# HGD_Update-20200515.net
KiCad netlist of a schematic drawn in Altium Designer
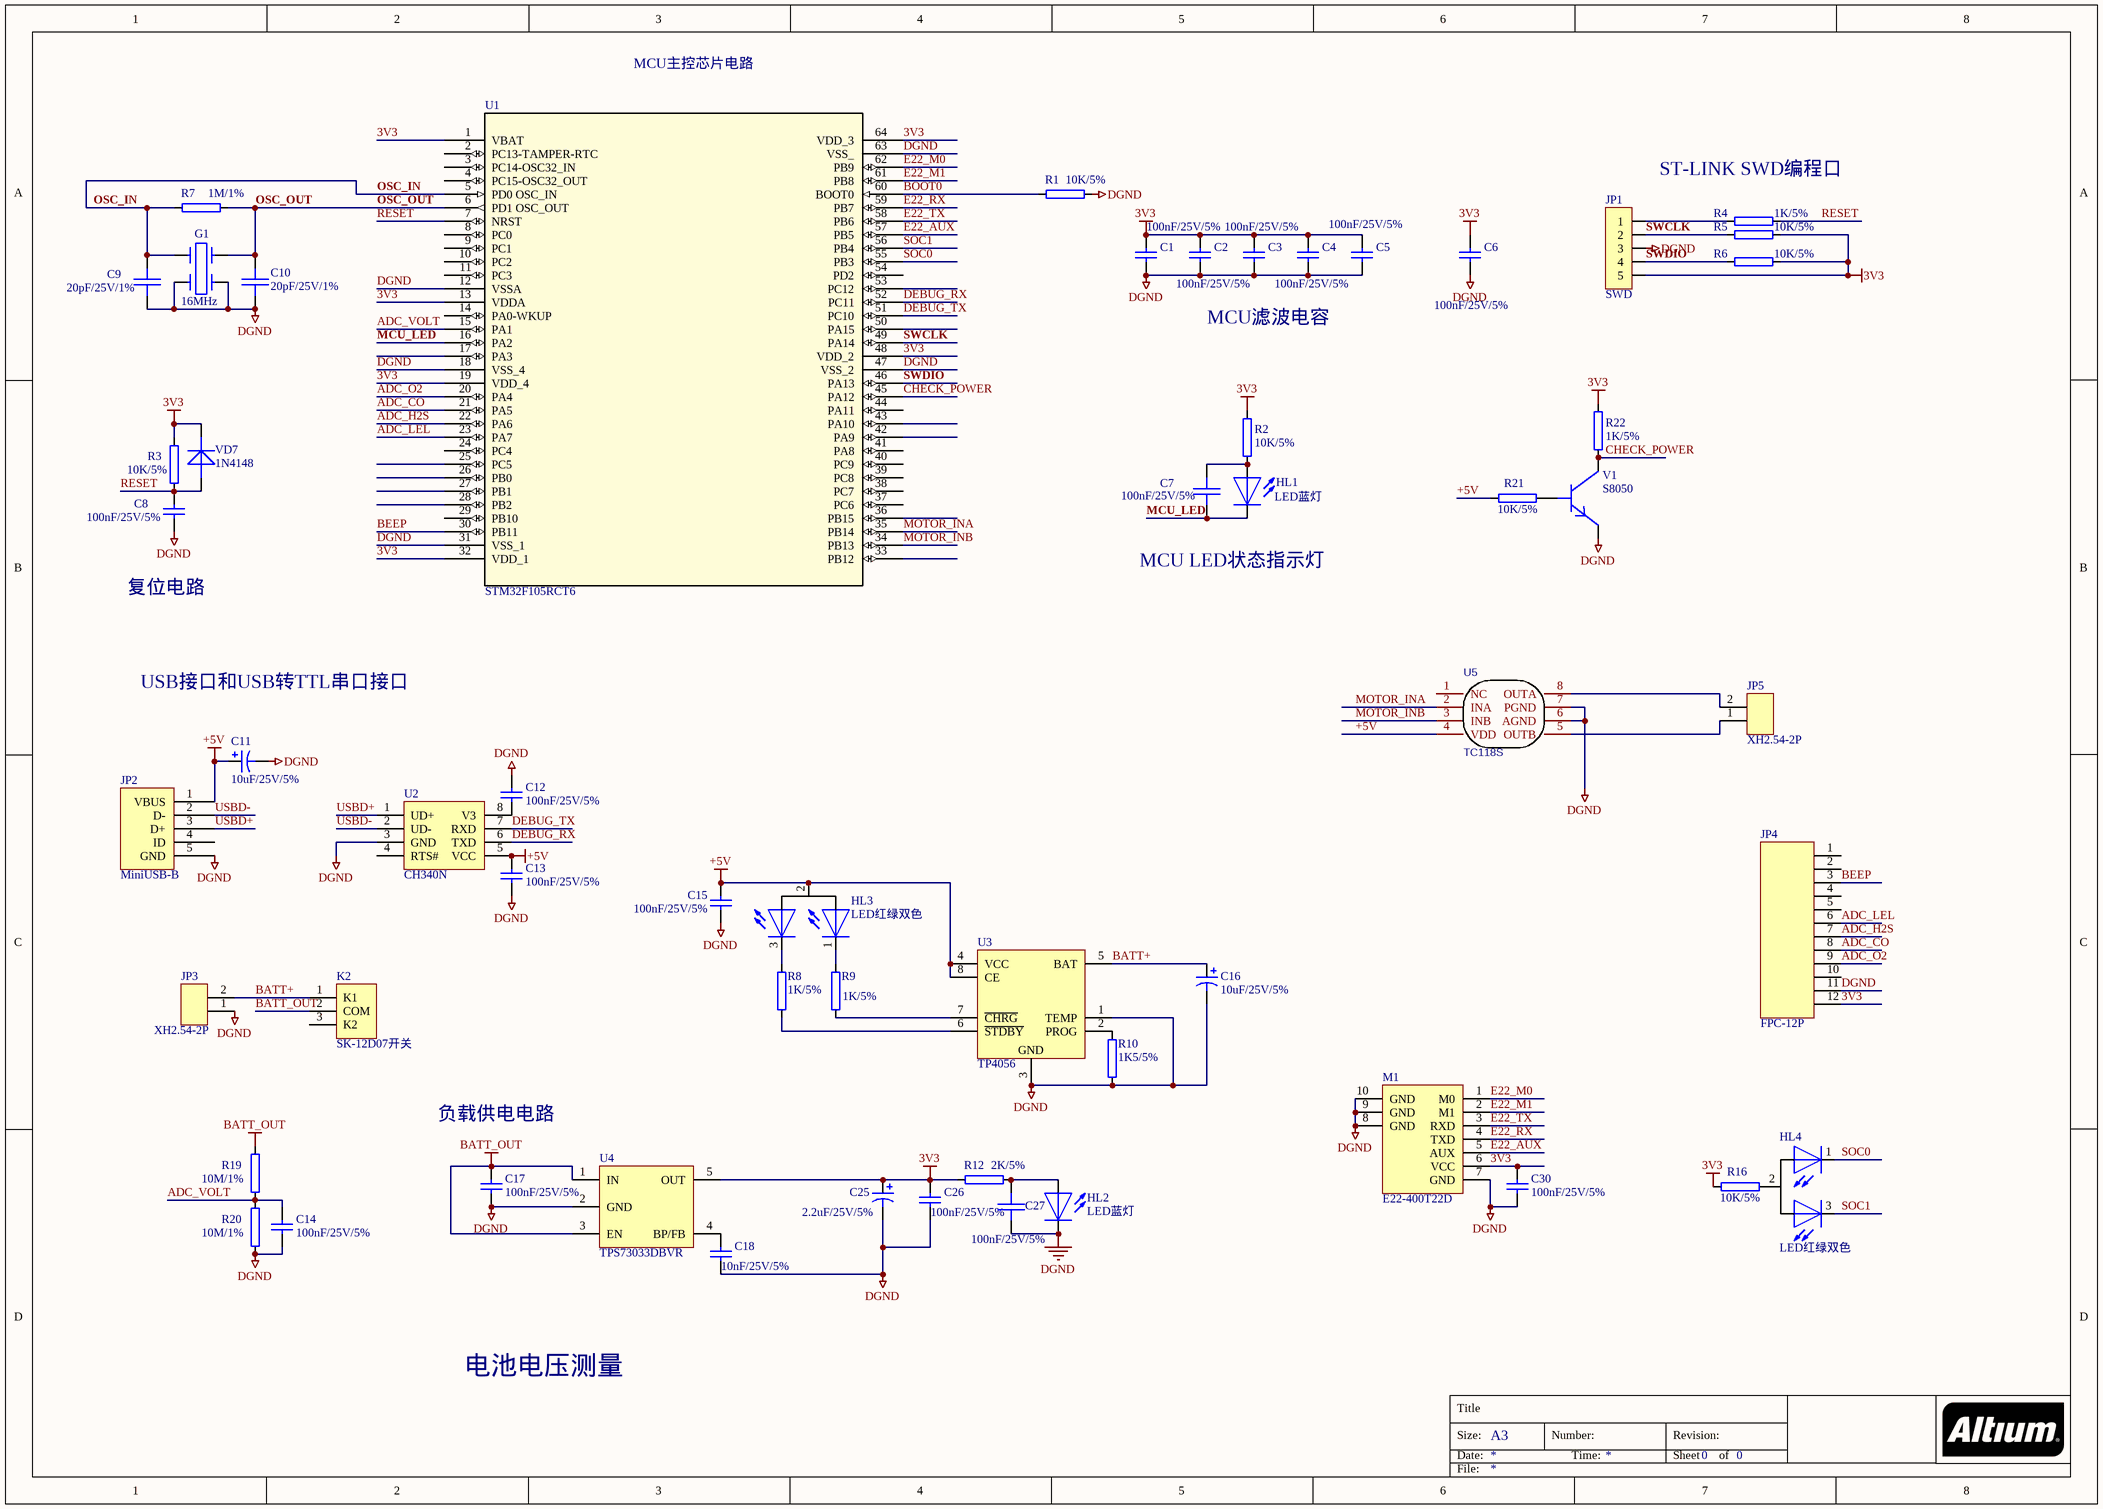
[diagram p0: HGD_Update-20200515.SchDoc]

(export (version "E")
  (design (tool "Eeschema 10.0.6"))
  (components
    (comp (ref "C1")
      (value "100nF/25V/5%")
      (footprint "C0603")
      (description "电容")
      (libsource (lib "*") (part "CAP-SMD"))
    )
    (comp (ref "C2")
      (value "100nF/25V/5%")
      (footprint "C0603")
      (description "电容")
      (libsource (lib "*") (part "CAP-SMD"))
    )
    (comp (ref "C3")
      (value "100nF/25V/5%")
      (footprint "C0603")
      (description "电容")
      (libsource (lib "*") (part "CAP-SMD"))
    )
    (comp (ref "C4")
      (value "100nF/25V/5%")
      (footprint "C0603")
      (description "电容")
      (libsource (lib "*") (part "CAP-SMD"))
    )
    (comp (ref "C5")
      (value "100nF/25V/5%")
      (footprint "C0603")
      (description "电容")
      (libsource (lib "*") (part "CAP-SMD"))
    )
    (comp (ref "C6")
      (value "100nF/25V/5%")
      (footprint "C0603")
      (description "电容")
      (libsource (lib "*") (part "CAP-SMD"))
    )
    (comp (ref "C7")
      (value "100nF/25V/5%")
      (footprint "C0603")
      (description "电容")
      (libsource (lib "*") (part "CAP"))
    )
    (comp (ref "C8")
      (value "100nF/25V/5%")
      (footprint "C0603")
      (description "电容")
      (libsource (lib "*") (part "CAP-SMD"))
    )
    (comp (ref "C9")
      (value "20pF/25V/1%")
      (footprint "C0603")
      (description "电容")
      (libsource (lib "ESSCH-Union") (part "CAP"))
    )
    (comp (ref "C10")
      (value "20pF/25V/1%")
      (footprint "C0603")
      (description "电容")
      (libsource (lib "ESSCH-Union") (part "CAP"))
    )
    (comp (ref "C11")
      (value "10uF/25V/5%")
      (footprint "C1206-1")
      (description "钽电容")
      (fields (field (name "PUBLISHER") "Altium Limited"))
      (libsource (lib "Miscellaneous Devices") (part "Cap Pol1"))
    )
    (comp (ref "C12")
      (value "100nF/25V/5%")
      (footprint "C0603")
      (description "电容")
      (fields (field (name "PUBLISHER") "Altium Limited"))
      (libsource (lib "Miscellaneous Devices") (part "Cap"))
    )
    (comp (ref "C13")
      (value "100nF/25V/5%")
      (footprint "C0603")
      (description "电容")
      (fields (field (name "PUBLISHER") "Altium Limited"))
      (libsource (lib "Miscellaneous Devices") (part "Cap"))
    )
    (comp (ref "C14") (value "100nF/25V/5%") (footprint "C0603") (libsource (lib "*") (part "CAP-SMD")))
    (comp (ref "C15")
      (value "100nF/25V/5%")
      (footprint "C0603")
      (description "电容")
      (fields (field (name "PUBLISHER") "Altium Limited"))
      (libsource (lib "Miscellaneous Devices") (part "Cap"))
    )
    (comp (ref "C16")
      (value "10uF/25V/5%")
      (footprint "C1206-1")
      (description "钽电容")
      (fields (field (name "PUBLISHER") "Altium Limited"))
      (libsource (lib "Miscellaneous Devices") (part "Cap Pol1"))
    )
    (comp (ref "C17") (value "100nF/25V/5%") (footprint "C0603") (libsource (lib "*") (part "CAP-SMD")))
    (comp (ref "C18")
      (value "10nF/25V/5%")
      (footprint "C0603")
      (description "电容")
      (fields (field (name "PUBLISHER") "Altium Limited"))
      (libsource (lib "Miscellaneous Devices") (part "Cap"))
    )
    (comp (ref "C25")
      (value "2.2uF/25V/5%")
      (footprint "C1206-1")
      (description "钽电容")
      (fields (field (name "PUBLISHER") "Altium Limited"))
      (libsource (lib "Miscellaneous Devices") (part "Cap Pol1"))
    )
    (comp (ref "C26")
      (value "100nF/25V/5%")
      (footprint "C0603")
      (description "电容")
      (fields (field (name "PUBLISHER") "Altium Limited"))
      (libsource (lib "Miscellaneous Devices") (part "Cap"))
    )
    (comp (ref "C27")
      (value "100nF/25V/5%")
      (footprint "C0603")
      (description "电容")
      (libsource (lib "*") (part "CAP"))
    )
    (comp (ref "C30")
      (value "100nF/25V/5%")
      (footprint "C0603")
      (description "电容")
      (fields (field (name "PUBLISHER") "Altium Limited"))
      (libsource (lib "Miscellaneous Devices") (part "Cap"))
    )
    (comp (ref "G1")
      (value "16MHz")
      (footprint "OSC5032")
      (description "两对电极压电晶体")
      (libsource (lib "ESSCH-Union") (part "CRYSTAL_4"))
    )
    (comp (ref "HL1")
      (value "LED蓝灯")
      (footprint "LED0603")
      (description "发光二极管")
      (libsource (lib "wypPCB_Lib") (part "发光二极管"))
    )
    (comp (ref "HL2")
      (value "LED蓝灯")
      (footprint "LED0603")
      (description "发光二极管")
      (libsource (lib "wypPCB_Lib") (part "发光二极管"))
    )
    (comp (ref "HL3")
      (value "LED红绿双色")
      (footprint "LED2_Common_Anode")
      (description "LED2_Common_Anode：双色LED，共阳极")
      (libsource (lib "") (part "LED2_Common_Anode_1"))
    )
    (comp (ref "HL4")
      (value "LED红绿双色")
      (footprint "LED2_Common_Anode")
      (description "LED2_Common_Anode：双色LED，共阳极")
      (libsource (lib "wypPCB_Lib") (part "LED2_Common_Anode"))
    )
    (comp (ref "JP1")
      (value "SWD")
      (footprint "XH2.54-5AW")
      (description "XH2.54-5P直插插针")
      (libsource (lib "wypPCB_Lib") (part "JP_XH2.54-5AW"))
    )
    (comp (ref "JP2")
      (value "MiniUSB-B")
      (footprint "MiniUSB-B")
      (description "MiniUSB-B母头插座")
      (libsource (lib "wypPCB_Lib") (part "MiniUSB-B"))
    )
    (comp (ref "JP3")
      (value "XH2.54-2P")
      (footprint "XH2.54-2AW")
      (description "XH2.54-2P弯针插座")
      (libsource (lib "") (part "XH2.54-2AW_1"))
    )
    (comp (ref "JP4")
      (value "FPC-12P")
      (footprint "FPC-1.0MM-12P-W")
      (libsource (lib "wypPCB_Lib") (part "FPC-12P"))
    )
    (comp (ref "JP5")
      (value "XH2.54-2P")
      (footprint "XH2.54-2AW")
      (description "XH2.54-2P弯针插座")
      (libsource (lib "wypPCB_Lib") (part "XH2.54-2AW"))
    )
    (comp (ref "K2")
      (value "SK-12D07开关")
      (footprint "SK-12D07")
      (description "SK-12D07：3脚2档小型拨动开关")
      (libsource (lib "WTME_PT100(v0.1)-20190512") (part "SK-12D07"))
    )
    (comp (ref "M1")
      (value "E22-400T22D")
      (footprint "E22-400T22D")
      (description "E22-400T22D LoRa模块")
      (libsource (lib "wypPCB_Lib") (part "E22-400T22D"))
    )
    (comp (ref "R1")
      (value "10K/5%")
      (footprint "R0603")
      (description "电阻")
      (libsource (lib "*") (part "RES2"))
    )
    (comp (ref "R2")
      (value "10K/5%")
      (footprint "R0603")
      (description "电阻")
      (libsource (lib "*") (part "RES2"))
    )
    (comp (ref "R3")
      (value "10K/5%")
      (footprint "R0603")
      (description "电阻")
      (libsource (lib "") (part "RES2_1"))
    )
    (comp (ref "R4")
      (value "1K/5%")
      (footprint "R0603")
      (description "电阻")
      (libsource (lib "") (part "RES2_1"))
    )
    (comp (ref "R5")
      (value "10K/5%")
      (footprint "R0603")
      (description "电阻")
      (libsource (lib "") (part "RES2_1"))
    )
    (comp (ref "R6")
      (value "10K/5%")
      (footprint "R0603")
      (description "电阻")
      (libsource (lib "") (part "RES2_1"))
    )
    (comp (ref "R7")
      (value "1M/1%")
      (footprint "R0603")
      (description "电阻")
      (libsource (lib "") (part "RES2_1"))
    )
    (comp (ref "R8")
      (value "1K/5%")
      (footprint "R0603")
      (description "电阻")
      (libsource (lib "") (part "RES2_2"))
    )
    (comp (ref "R9")
      (value "1K/5%")
      (footprint "R0603")
      (description "电阻")
      (libsource (lib "") (part "RES2_2"))
    )
    (comp (ref "R10")
      (value "1K5/5%")
      (footprint "R0603")
      (description "电阻")
      (libsource (lib "") (part "RES2_2"))
    )
    (comp (ref "R12")
      (value "2K/5%")
      (footprint "R0603")
      (description "电阻")
      (libsource (lib "*") (part "RES2"))
    )
    (comp (ref "R16")
      (value "10K/5%")
      (footprint "R0603")
      (description "电阻")
      (libsource (lib "*") (part "RES2"))
    )
    (comp (ref "R19")
      (value "10M/1%")
      (footprint "R0603")
      (description "电阻")
      (libsource (lib "*") (part "RES2"))
    )
    (comp (ref "R20")
      (value "10M/1%")
      (footprint "R0603")
      (description "电阻")
      (libsource (lib "*") (part "RES2"))
    )
    (comp (ref "R21")
      (value "10K/5%")
      (footprint "R0603")
      (description "电阻")
      (libsource (lib "") (part "RES2_1"))
    )
    (comp (ref "R22")
      (value "1K/5%")
      (footprint "R0603")
      (description "电阻")
      (libsource (lib "") (part "RES2_2"))
    )
    (comp (ref "U1")
      (value "STM32F105RCT6")
      (footprint "LQFP64_STM32F105R")
      (libsource (lib "wypPCB_Lib") (part "STM32F105RCT6"))
    )
    (comp (ref "U2")
      (value "CH340N")
      (footprint "CH340N_SOP8")
      (libsource (lib "wypPCB_Lib") (part "CH340N"))
    )
    (comp (ref "U3")
      (value "TP4056")
      (footprint "TP4056_SOP8_SOP127P600X175-8N")
      (libsource (lib "wypPCB_Lib") (part "TP4056"))
    )
    (comp (ref "U4")
      (value "TPS73033DBVR")
      (footprint "SGM2019_SOT23-5_95P280X125-5N")
      (description "SGM2019：Low Power, Low Dropout, RF Linear Regulators")
      (libsource (lib "wypPCB_Lib") (part "SGM2019"))
    )
    (comp (ref "U5")
      (value "TC118S")
      (footprint "SOP-8_L4.9-W3.9-P1.27-LS6.0-BL")
      (fields (field (name "BOM_SUPPLIER PART") "C88308"))
      (libsource (lib "HGD_Update_20200515") (part "TC118S"))
    )
    (comp (ref "V1")
      (value "S8050")
      (footprint "SOT-23")
      (description "NPN三极管")
      (libsource (lib "ESLIB(v1.1)-AD9-20150731") (part "NPN"))
    )
    (comp (ref "VD7")
      (value "1N4148")
      (footprint "LL-34")
      (description "开关二极管")
      (libsource (lib "wypPCB_Lib") (part "开关二极管"))
    )
  )
  (nets
    (net (code "1") (name "+5V") (class "Default")
      (node (ref "C11") (pin "1") (pinfunction "1_1") (pintype "passive"))
      (node (ref "C13") (pin "1") (pinfunction "1_1") (pintype "passive"))
      (node (ref "C15") (pin "1") (pinfunction "1_1") (pintype "passive"))
      (node (ref "HL3") (pin "2") (pinfunction "A_2") (pintype "passive"))
      (node (ref "JP2") (pin "1") (pinfunction "VBUS_1") (pintype "passive"))
      (node (ref "R21") (pin "2") (pintype "passive"))
      (node (ref "U2") (pin "5") (pinfunction "VCC_5") (pintype "passive"))
      (node (ref "U3") (pin "4") (pinfunction "VCC_4") (pintype "passive"))
      (node (ref "U3") (pin "8") (pinfunction "CE_8") (pintype "passive"))
      (node (ref "U5") (pin "4") (pinfunction "VDD_4") (pintype "passive"))
    )
    (net (code "2") (name "/ADC_CO") (class "Default")
      (node (ref "JP4") (pin "8") (pintype "passive"))
      (node (ref "U1") (pin "21") (pinfunction "PA5_21") (pintype "bidirectional"))
    )
    (net (code "3") (name "/ADC_H2S") (class "Default")
      (node (ref "JP4") (pin "7") (pintype "passive"))
      (node (ref "U1") (pin "22") (pinfunction "PA6_22") (pintype "bidirectional"))
    )
    (net (code "4") (name "/ADC_LEL") (class "Default")
      (node (ref "JP4") (pin "6") (pintype "passive"))
      (node (ref "U1") (pin "23") (pinfunction "PA7_23") (pintype "bidirectional"))
    )
    (net (code "5") (name "/ADC_O2") (class "Default")
      (node (ref "JP4") (pin "9") (pintype "passive"))
      (node (ref "U1") (pin "20") (pinfunction "PA4_20") (pintype "bidirectional"))
    )
    (net (code "6") (name "/ADC_VOLT") (class "Default")
      (node (ref "C14") (pin "1") (pintype "passive"))
      (node (ref "R19") (pin "2") (pintype "passive"))
      (node (ref "R20") (pin "1") (pintype "passive"))
      (node (ref "U1") (pin "15") (pinfunction "PA1_15") (pintype "bidirectional"))
    )
    (net (code "7") (name "/BATT+") (class "Default")
      (node (ref "C16") (pin "1") (pinfunction "1_1") (pintype "passive"))
      (node (ref "JP3") (pin "2") (pintype "passive"))
      (node (ref "K2") (pin "1") (pinfunction "K1_1") (pintype "passive"))
      (node (ref "U3") (pin "5") (pinfunction "BAT_5") (pintype "passive"))
    )
    (net (code "8") (name "/BEEP") (class "Default")
      (node (ref "JP4") (pin "3") (pintype "passive"))
      (node (ref "U1") (pin "30") (pinfunction "PB11_30") (pintype "bidirectional"))
    )
    (net (code "9") (name "/BOOT0") (class "Default")
      (node (ref "R1") (pin "2") (pintype "passive"))
      (node (ref "U1") (pin "60") (pinfunction "BOOT0_60") (pintype "input"))
    )
    (net (code "10") (name "/CHECK_POWER") (class "Default")
      (node (ref "R22") (pin "2") (pintype "passive"))
      (node (ref "U1") (pin "45") (pinfunction "PA12_45") (pintype "bidirectional"))
      (node (ref "V1") (pin "C") (pintype "passive"))
    )
    (net (code "11") (name "/DEBUG_RX") (class "Default")
      (node (ref "U1") (pin "52") (pinfunction "PC11_52") (pintype "bidirectional"))
      (node (ref "U2") (pin "6") (pinfunction "TXD_6") (pintype "passive"))
    )
    (net (code "12") (name "/DEBUG_TX") (class "Default")
      (node (ref "U1") (pin "51") (pinfunction "PC10_51") (pintype "bidirectional"))
      (node (ref "U2") (pin "7") (pinfunction "RXD_7") (pintype "passive"))
    )
    (net (code "13") (name "/E22_AUX") (class "Default")
      (node (ref "M1") (pin "5") (pinfunction "AUX_5") (pintype "passive"))
      (node (ref "U1") (pin "57") (pinfunction "PB5_57") (pintype "bidirectional"))
    )
    (net (code "14") (name "/E22_M0") (class "Default")
      (node (ref "M1") (pin "1") (pinfunction "M0_1") (pintype "passive"))
      (node (ref "U1") (pin "62") (pinfunction "PB9_62") (pintype "bidirectional"))
    )
    (net (code "15") (name "/E22_M1") (class "Default")
      (node (ref "M1") (pin "2") (pinfunction "M1_2") (pintype "passive"))
      (node (ref "U1") (pin "61") (pinfunction "PB8_61") (pintype "bidirectional"))
    )
    (net (code "16") (name "/E22_RX") (class "Default")
      (node (ref "M1") (pin "4") (pinfunction "TXD_4") (pintype "passive"))
      (node (ref "U1") (pin "59") (pinfunction "PB7_59") (pintype "bidirectional"))
    )
    (net (code "17") (name "/E22_TX") (class "Default")
      (node (ref "M1") (pin "3") (pinfunction "RXD_3") (pintype "passive"))
      (node (ref "U1") (pin "58") (pinfunction "PB6_58") (pintype "bidirectional"))
    )
    (net (code "18") (name "/MCU_LED") (class "Default")
      (node (ref "C7") (pin "2") (pintype "passive"))
      (node (ref "HL1") (pin "K") (pintype "passive"))
      (node (ref "U1") (pin "16") (pinfunction "PA2_16") (pintype "bidirectional"))
    )
    (net (code "19") (name "/MOTOR_INA") (class "Default")
      (node (ref "U1") (pin "35") (pinfunction "PB14_35") (pintype "bidirectional"))
      (node (ref "U5") (pin "2") (pinfunction "INA_2") (pintype "passive"))
    )
    (net (code "20") (name "/MOTOR_INB") (class "Default")
      (node (ref "U1") (pin "34") (pinfunction "PB13_34") (pintype "bidirectional"))
      (node (ref "U5") (pin "3") (pinfunction "INB_3") (pintype "passive"))
    )
    (net (code "21") (name "/OSC_IN") (class "Default")
      (node (ref "C9") (pin "2") (pintype "passive"))
      (node (ref "G1") (pin "1") (pintype "passive"))
      (node (ref "R7") (pin "1") (pintype "passive"))
      (node (ref "U1") (pin "5") (pinfunction "PD0_OSC_IN_5") (pintype "input"))
    )
    (net (code "22") (name "/OSC_OUT") (class "Default")
      (node (ref "C10") (pin "1") (pintype "passive"))
      (node (ref "G1") (pin "3") (pintype "passive"))
      (node (ref "R7") (pin "2") (pintype "passive"))
      (node (ref "U1") (pin "6") (pinfunction "PD1_OSC_OUT_6") (pintype "output"))
    )
    (net (code "23") (name "/RESET") (class "Default")
      (node (ref "C8") (pin "1") (pintype "passive"))
      (node (ref "R3") (pin "1") (pintype "passive"))
      (node (ref "R4") (pin "2") (pintype "passive"))
      (node (ref "U1") (pin "7") (pinfunction "NRST_7") (pintype "bidirectional"))
      (node (ref "VD7") (pin "A") (pintype "passive"))
    )
    (net (code "24") (name "/SOC0") (class "Default")
      (node (ref "HL4") (pin "1") (pinfunction "K1_1") (pintype "passive"))
      (node (ref "U1") (pin "55") (pinfunction "PB3_55") (pintype "bidirectional"))
    )
    (net (code "25") (name "/SOC1") (class "Default")
      (node (ref "HL4") (pin "3") (pinfunction "K2_3") (pintype "passive"))
      (node (ref "U1") (pin "56") (pinfunction "PB4_56") (pintype "bidirectional"))
    )
    (net (code "26") (name "/SWCLK") (class "Default")
      (node (ref "JP1") (pin "2") (pinfunction "2_2") (pintype "passive"))
      (node (ref "R5") (pin "1") (pintype "passive"))
      (node (ref "U1") (pin "49") (pinfunction "PA14_49") (pintype "bidirectional"))
    )
    (net (code "27") (name "/SWDIO") (class "Default")
      (node (ref "JP1") (pin "4") (pinfunction "4_4") (pintype "passive"))
      (node (ref "R6") (pin "1") (pintype "passive"))
      (node (ref "U1") (pin "46") (pinfunction "PA13_46") (pintype "bidirectional"))
    )
    (net (code "28") (name "/USBD+") (class "Default")
      (node (ref "JP2") (pin "3") (pinfunction "D+_3") (pintype "passive"))
      (node (ref "U2") (pin "1") (pinfunction "UD+_1") (pintype "passive"))
    )
    (net (code "29") (name "/USBD-") (class "Default")
      (node (ref "JP2") (pin "2") (pinfunction "D-_2") (pintype "passive"))
      (node (ref "U2") (pin "2") (pinfunction "UD-_2") (pintype "passive"))
    )
    (net (code "30") (name "3V3") (class "Default")
      (node (ref "C1") (pin "2") (pintype "passive"))
      (node (ref "C2") (pin "1") (pintype "passive"))
      (node (ref "C25") (pin "1") (pinfunction "1_1") (pintype "passive"))
      (node (ref "C26") (pin "2") (pinfunction "2_2") (pintype "passive"))
      (node (ref "C3") (pin "1") (pintype "passive"))
      (node (ref "C30") (pin "2") (pinfunction "2_2") (pintype "passive"))
      (node (ref "C4") (pin "2") (pintype "passive"))
      (node (ref "C5") (pin "2") (pintype "passive"))
      (node (ref "C6") (pin "2") (pintype "passive"))
      (node (ref "JP1") (pin "5") (pinfunction "5_5") (pintype "passive"))
      (node (ref "JP4") (pin "12") (pintype "passive"))
      (node (ref "M1") (pin "6") (pinfunction "VCC_6") (pintype "passive"))
      (node (ref "R12") (pin "1") (pintype "passive"))
      (node (ref "R16") (pin "1") (pintype "passive"))
      (node (ref "R2") (pin "1") (pintype "passive"))
      (node (ref "R22") (pin "1") (pintype "passive"))
      (node (ref "R3") (pin "2") (pintype "passive"))
      (node (ref "R5") (pin "2") (pintype "passive"))
      (node (ref "R6") (pin "2") (pintype "passive"))
      (node (ref "U1") (pin "1") (pinfunction "VBAT_1") (pintype "power_in"))
      (node (ref "U1") (pin "13") (pinfunction "VDDA_13") (pintype "power_in"))
      (node (ref "U1") (pin "19") (pinfunction "VDD_4_19") (pintype "power_in"))
      (node (ref "U1") (pin "32") (pinfunction "VDD_1_32") (pintype "power_in"))
      (node (ref "U1") (pin "48") (pinfunction "VDD_2_48") (pintype "power_in"))
      (node (ref "U1") (pin "64") (pinfunction "VDD_3_64") (pintype "power_in"))
      (node (ref "U4") (pin "5") (pinfunction "OUT_5") (pintype "passive"))
      (node (ref "VD7") (pin "K") (pintype "passive"))
    )
    (net (code "31") (name "BATT_OUT") (class "Default")
      (node (ref "C17") (pin "1") (pintype "passive"))
      (node (ref "K2") (pin "2") (pinfunction "COM_2") (pintype "passive"))
      (node (ref "R19") (pin "1") (pintype "passive"))
      (node (ref "U4") (pin "1") (pinfunction "IN_1") (pintype "passive"))
      (node (ref "U4") (pin "3") (pinfunction "EN_3") (pintype "passive"))
    )
    (net (code "32") (name "DGND") (class "Default")
      (node (ref "C1") (pin "1") (pintype "passive"))
      (node (ref "C10") (pin "2") (pintype "passive"))
      (node (ref "C11") (pin "2") (pinfunction "2_2") (pintype "passive"))
      (node (ref "C12") (pin "1") (pinfunction "1_1") (pintype "passive"))
      (node (ref "C13") (pin "2") (pinfunction "2_2") (pintype "passive"))
      (node (ref "C14") (pin "2") (pintype "passive"))
      (node (ref "C15") (pin "2") (pinfunction "2_2") (pintype "passive"))
      (node (ref "C16") (pin "2") (pinfunction "2_2") (pintype "passive"))
      (node (ref "C17") (pin "2") (pintype "passive"))
      (node (ref "C18") (pin "1") (pinfunction "1_1") (pintype "passive"))
      (node (ref "C2") (pin "2") (pintype "passive"))
      (node (ref "C25") (pin "2") (pinfunction "2_2") (pintype "passive"))
      (node (ref "C26") (pin "1") (pinfunction "1_1") (pintype "passive"))
      (node (ref "C27") (pin "2") (pintype "passive"))
      (node (ref "C3") (pin "2") (pintype "passive"))
      (node (ref "C30") (pin "1") (pinfunction "1_1") (pintype "passive"))
      (node (ref "C4") (pin "1") (pintype "passive"))
      (node (ref "C5") (pin "1") (pintype "passive"))
      (node (ref "C6") (pin "1") (pintype "passive"))
      (node (ref "C8") (pin "2") (pintype "passive"))
      (node (ref "C9") (pin "1") (pintype "passive"))
      (node (ref "G1") (pin "2") (pintype "passive"))
      (node (ref "G1") (pin "4") (pintype "passive"))
      (node (ref "HL2") (pin "K") (pintype "passive"))
      (node (ref "JP1") (pin "3") (pinfunction "3_3") (pintype "passive"))
      (node (ref "JP2") (pin "5") (pinfunction "GND_5") (pintype "passive"))
      (node (ref "JP3") (pin "1") (pintype "passive"))
      (node (ref "JP4") (pin "11") (pintype "passive"))
      (node (ref "M1") (pin "10") (pinfunction "GND_10") (pintype "passive"))
      (node (ref "M1") (pin "7") (pinfunction "GND_7") (pintype "passive"))
      (node (ref "M1") (pin "8") (pinfunction "GND_8") (pintype "passive"))
      (node (ref "M1") (pin "9") (pinfunction "GND_9") (pintype "passive"))
      (node (ref "R1") (pin "1") (pintype "passive"))
      (node (ref "R10") (pin "1") (pintype "passive"))
      (node (ref "R20") (pin "2") (pintype "passive"))
      (node (ref "U1") (pin "12") (pinfunction "VSSA_12") (pintype "power_in"))
      (node (ref "U1") (pin "18") (pinfunction "VSS_4_18") (pintype "power_in"))
      (node (ref "U1") (pin "31") (pinfunction "VSS_1_31") (pintype "power_in"))
      (node (ref "U1") (pin "47") (pinfunction "VSS_2_47") (pintype "power_in"))
      (node (ref "U1") (pin "63") (pinfunction "VSS__63") (pintype "power_in"))
      (node (ref "U2") (pin "3") (pinfunction "GND_3") (pintype "passive"))
      (node (ref "U3") (pin "1") (pinfunction "TEMP_1") (pintype "passive"))
      (node (ref "U3") (pin "3") (pinfunction "GND_3") (pintype "passive"))
      (node (ref "U4") (pin "2") (pinfunction "GND_2") (pintype "passive"))
      (node (ref "U5") (pin "6") (pinfunction "AGND_6") (pintype "passive"))
      (node (ref "U5") (pin "7") (pinfunction "PGND_7") (pintype "passive"))
      (node (ref "V1") (pin "E") (pintype "passive"))
    )
    (net (code "33") (name "Net-(C7-Pad1)") (class "Default")
      (node (ref "C7") (pin "1") (pintype "passive"))
      (node (ref "HL1") (pin "A") (pintype "passive"))
      (node (ref "R2") (pin "2") (pintype "passive"))
    )
    (net (code "34") (name "Net-(C27-Pad1)") (class "Default")
      (node (ref "C27") (pin "1") (pintype "passive"))
      (node (ref "HL2") (pin "A") (pintype "passive"))
      (node (ref "R12") (pin "2") (pintype "passive"))
    )
    (net (code "35") (name "Net-(HL3-K1)") (class "Default")
      (node (ref "HL3") (pin "1") (pinfunction "K1_1") (pintype "passive"))
      (node (ref "R9") (pin "2") (pintype "passive"))
    )
    (net (code "36") (name "Net-(HL3-K2)") (class "Default")
      (node (ref "HL3") (pin "3") (pinfunction "K2_3") (pintype "passive"))
      (node (ref "R8") (pin "2") (pintype "passive"))
    )
    (net (code "37") (name "Net-(HL4-A)") (class "Default")
      (node (ref "HL4") (pin "2") (pinfunction "A_2") (pintype "passive"))
      (node (ref "R16") (pin "2") (pintype "passive"))
    )
    (net (code "38") (name "Net-(JP1-Pad1)") (class "Default")
      (node (ref "JP1") (pin "1") (pinfunction "1_1") (pintype "passive"))
      (node (ref "R4") (pin "1") (pintype "passive"))
    )
    (net (code "39") (name "Net-(R21-Pad1)") (class "Default")
      (node (ref "R21") (pin "1") (pintype "passive"))
      (node (ref "V1") (pin "B") (pintype "passive"))
    )
    (net (code "40") (name "Net-(U2-V3)") (class "Default")
      (node (ref "C12") (pin "2") (pinfunction "2_2") (pintype "passive"))
      (node (ref "U2") (pin "8") (pinfunction "V3_8") (pintype "passive"))
    )
    (net (code "41") (name "Net-(U3-PROG)") (class "Default")
      (node (ref "R10") (pin "2") (pintype "passive"))
      (node (ref "U3") (pin "2") (pinfunction "PROG_2") (pintype "passive"))
    )
    (net (code "42") (name "Net-(U3-~{CHRG})") (class "Default")
      (node (ref "R9") (pin "1") (pintype "passive"))
      (node (ref "U3") (pin "7") (pinfunction "~{CHRG}_7") (pintype "passive"))
    )
    (net (code "43") (name "Net-(U3-~{STDBY})") (class "Default")
      (node (ref "R8") (pin "1") (pintype "passive"))
      (node (ref "U3") (pin "6") (pinfunction "~{STDBY}_6") (pintype "passive"))
    )
    (net (code "44") (name "Net-(U4-BP{slash}FB)") (class "Default")
      (node (ref "C18") (pin "2") (pinfunction "2_2") (pintype "passive"))
      (node (ref "U4") (pin "4") (pinfunction "BP/FB_4") (pintype "passive"))
    )
    (net (code "45") (name "Net-(U5-OUTA)") (class "Default")
      (node (ref "JP5") (pin "2") (pintype "passive"))
      (node (ref "U5") (pin "8") (pinfunction "OUTA_8") (pintype "passive"))
    )
    (net (code "46") (name "Net-(U5-OUTB)") (class "Default")
      (node (ref "JP5") (pin "1") (pintype "passive"))
      (node (ref "U5") (pin "5") (pinfunction "OUTB_5") (pintype "passive"))
    )
    (net (code "47") (name "unconnected-(JP2-ID-Pad4)") (class "Default")
      (node (ref "JP2") (pin "4") (pinfunction "ID_4") (pintype "passive"))
    )
    (net (code "48") (name "unconnected-(JP4-Pad1)") (class "Default")
      (node (ref "JP4") (pin "1") (pintype "passive"))
    )
    (net (code "49") (name "unconnected-(JP4-Pad2)") (class "Default")
      (node (ref "JP4") (pin "2") (pintype "passive"))
    )
    (net (code "50") (name "unconnected-(JP4-Pad4)") (class "Default")
      (node (ref "JP4") (pin "4") (pintype "passive"))
    )
    (net (code "51") (name "unconnected-(JP4-Pad5)") (class "Default")
      (node (ref "JP4") (pin "5") (pintype "passive"))
    )
    (net (code "52") (name "unconnected-(JP4-Pad10)") (class "Default")
      (node (ref "JP4") (pin "10") (pintype "passive"))
    )
    (net (code "53") (name "unconnected-(K2-K2-Pad3)") (class "Default")
      (node (ref "K2") (pin "3") (pinfunction "K2_3") (pintype "passive"))
    )
    (net (code "54") (name "unconnected-(U1-PA0-WKUP-Pad14)") (class "Default")
      (node (ref "U1") (pin "14") (pinfunction "PA0-WKUP_14") (pintype "bidirectional"))
    )
    (net (code "55") (name "unconnected-(U1-PA3-Pad17)") (class "Default")
      (node (ref "U1") (pin "17") (pinfunction "PA3_17") (pintype "bidirectional"))
    )
    (net (code "56") (name "unconnected-(U1-PA8-Pad41)") (class "Default")
      (node (ref "U1") (pin "41") (pinfunction "PA8_41") (pintype "bidirectional"))
    )
    (net (code "57") (name "unconnected-(U1-PA9-Pad42)") (class "Default")
      (node (ref "U1") (pin "42") (pinfunction "PA9_42") (pintype "bidirectional"))
    )
    (net (code "58") (name "unconnected-(U1-PA10-Pad43)") (class "Default")
      (node (ref "U1") (pin "43") (pinfunction "PA10_43") (pintype "bidirectional"))
    )
    (net (code "59") (name "unconnected-(U1-PA11-Pad44)") (class "Default")
      (node (ref "U1") (pin "44") (pinfunction "PA11_44") (pintype "bidirectional"))
    )
    (net (code "60") (name "unconnected-(U1-PA15-Pad50)") (class "Default")
      (node (ref "U1") (pin "50") (pinfunction "PA15_50") (pintype "bidirectional"))
    )
    (net (code "61") (name "unconnected-(U1-PB0-Pad26)") (class "Default")
      (node (ref "U1") (pin "26") (pinfunction "PB0_26") (pintype "bidirectional"))
    )
    (net (code "62") (name "unconnected-(U1-PB1-Pad27)") (class "Default")
      (node (ref "U1") (pin "27") (pinfunction "PB1_27") (pintype "bidirectional"))
    )
    (net (code "63") (name "unconnected-(U1-PB2-Pad28)") (class "Default")
      (node (ref "U1") (pin "28") (pinfunction "PB2_28") (pintype "bidirectional"))
    )
    (net (code "64") (name "unconnected-(U1-PB10-Pad29)") (class "Default")
      (node (ref "U1") (pin "29") (pinfunction "PB10_29") (pintype "bidirectional"))
    )
    (net (code "65") (name "unconnected-(U1-PB12-Pad33)") (class "Default")
      (node (ref "U1") (pin "33") (pinfunction "PB12_33") (pintype "bidirectional"))
    )
    (net (code "66") (name "unconnected-(U1-PB15-Pad36)") (class "Default")
      (node (ref "U1") (pin "36") (pinfunction "PB15_36") (pintype "bidirectional"))
    )
    (net (code "67") (name "unconnected-(U1-PC0-Pad8)") (class "Default")
      (node (ref "U1") (pin "8") (pinfunction "PC0_8") (pintype "bidirectional"))
    )
    (net (code "68") (name "unconnected-(U1-PC1-Pad9)") (class "Default")
      (node (ref "U1") (pin "9") (pinfunction "PC1_9") (pintype "bidirectional"))
    )
    (net (code "69") (name "unconnected-(U1-PC2-Pad10)") (class "Default")
      (node (ref "U1") (pin "10") (pinfunction "PC2_10") (pintype "bidirectional"))
    )
    (net (code "70") (name "unconnected-(U1-PC3-Pad11)") (class "Default")
      (node (ref "U1") (pin "11") (pinfunction "PC3_11") (pintype "bidirectional"))
    )
    (net (code "71") (name "unconnected-(U1-PC4-Pad24)") (class "Default")
      (node (ref "U1") (pin "24") (pinfunction "PC4_24") (pintype "bidirectional"))
    )
    (net (code "72") (name "unconnected-(U1-PC5-Pad25)") (class "Default")
      (node (ref "U1") (pin "25") (pinfunction "PC5_25") (pintype "bidirectional"))
    )
    (net (code "73") (name "unconnected-(U1-PC6-Pad37)") (class "Default")
      (node (ref "U1") (pin "37") (pinfunction "PC6_37") (pintype "bidirectional"))
    )
    (net (code "74") (name "unconnected-(U1-PC7-Pad38)") (class "Default")
      (node (ref "U1") (pin "38") (pinfunction "PC7_38") (pintype "bidirectional"))
    )
    (net (code "75") (name "unconnected-(U1-PC8-Pad39)") (class "Default")
      (node (ref "U1") (pin "39") (pinfunction "PC8_39") (pintype "bidirectional"))
    )
    (net (code "76") (name "unconnected-(U1-PC9-Pad40)") (class "Default")
      (node (ref "U1") (pin "40") (pinfunction "PC9_40") (pintype "bidirectional"))
    )
    (net (code "77") (name "unconnected-(U1-PC12-Pad53)") (class "Default")
      (node (ref "U1") (pin "53") (pinfunction "PC12_53") (pintype "bidirectional"))
    )
    (net (code "78") (name "unconnected-(U1-PC13-TAMPER-RTC-Pad2)") (class "Default")
      (node (ref "U1") (pin "2") (pinfunction "PC13-TAMPER-RTC_2") (pintype "bidirectional"))
    )
    (net (code "79") (name "unconnected-(U1-PC14-OSC32_IN-Pad3)") (class "Default")
      (node (ref "U1") (pin "3") (pinfunction "PC14-OSC32_IN_3") (pintype "bidirectional"))
    )
    (net (code "80") (name "unconnected-(U1-PC15-OSC32_OUT-Pad4)") (class "Default")
      (node (ref "U1") (pin "4") (pinfunction "PC15-OSC32_OUT_4") (pintype "bidirectional"))
    )
    (net (code "81") (name "unconnected-(U1-PD2-Pad54)") (class "Default")
      (node (ref "U1") (pin "54") (pinfunction "PD2_54") (pintype "bidirectional"))
    )
    (net (code "82") (name "unconnected-(U2-RTS#-Pad4)") (class "Default")
      (node (ref "U2") (pin "4") (pinfunction "RTS#_4") (pintype "passive"))
    )
    (net (code "83") (name "unconnected-(U5-NC-Pad1)") (class "Default")
      (node (ref "U5") (pin "1") (pinfunction "NC_1") (pintype "passive"))
    )
  )
)
